# PoE.net
KiCad netlist of a schematic drawn in Altium Designer
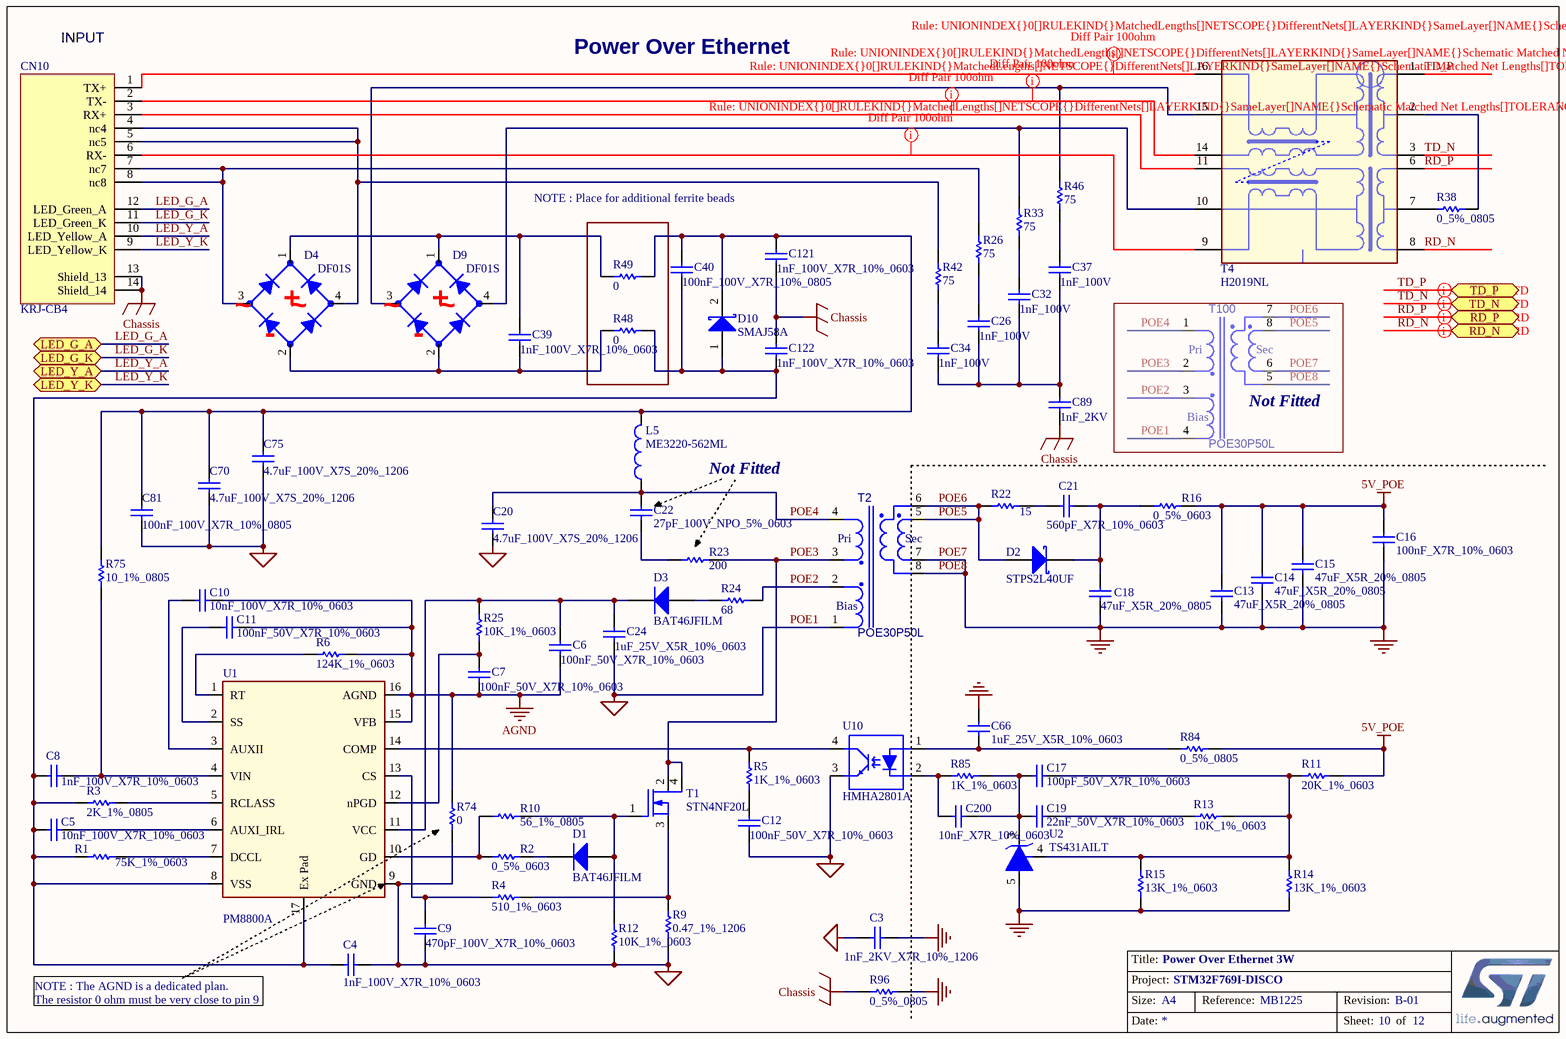
[diagram p0: PoE.SchDoc]

(export (version "E")
  (design (tool "Eeschema 10.0.6"))
  (components
    (comp (ref "C3")
      (value "1nF_2KV_X7R_10%_1206")
      (footprint "1206C")
      (description "Capacitor,1nF,2KV,X7R,10%,1206,YAGEO")
      (libsource (lib "MCD_TOOLS_CAPACITOR") (part "Cap_1nF_2KV_X7R_10%_1206"))
    )
    (comp (ref "C4")
      (value "1nF_100V_X7R_10%_0603")
      (footprint "0603C")
      (description "Capacitor,1nF,100V,X7R,10%,0603,YAGEO")
      (libsource (lib "MCD_TOOLS_CAPACITOR") (part "Cap_1nF_100V_X7R_10%_0603"))
    )
    (comp (ref "C5")
      (value "10nF_100V_X7R_10%_0603")
      (footprint "0603C")
      (description "Capacitor,10nF,100V,X7R,10%,0603,YAGEO")
      (libsource (lib "MCD_TOOLS_CAPACITOR") (part "Cap_10nF_100V_X7R_10%_0603"))
    )
    (comp (ref "C6")
      (value "100nF_50V_X7R_10%_0603")
      (footprint "0603C")
      (description "Capacitor,100nF,50V,X7R,10%,0603,YAGEO")
      (libsource (lib "MCD_TOOLS_CAPACITOR") (part "Cap_100nF_50V_X7R_10%_0603"))
    )
    (comp (ref "C7")
      (value "100nF_50V_X7R_10%_0603")
      (footprint "0603C")
      (description "Capacitor,100nF,50V,X7R,10%,0603,YAGEO")
      (libsource (lib "MCD_TOOLS_CAPACITOR") (part "Cap_100nF_50V_X7R_10%_0603"))
    )
    (comp (ref "C8")
      (value "1nF_100V_X7R_10%_0603")
      (footprint "0603C")
      (description "Capacitor,1nF,100V,X7R,10%,0603,YAGEO")
      (libsource (lib "MCD_TOOLS_CAPACITOR") (part "Cap_1nF_100V_X7R_10%_0603"))
    )
    (comp (ref "C9")
      (value "470pF_100V_X7R_10%_0603")
      (footprint "0603C")
      (description "Capacitor,470pF,100V,X7R,10%,0603,AVX")
      (libsource (lib "MCD_TOOLS_CAPACITOR") (part "Cap_470pF_100V_X7R_10%_0603"))
    )
    (comp (ref "C10")
      (value "10nF_100V_X7R_10%_0603")
      (footprint "0603C")
      (description "Capacitor,10nF,100V,X7R,10%,0603,YAGEO")
      (libsource (lib "MCD_TOOLS_CAPACITOR") (part "Cap_10nF_100V_X7R_10%_0603"))
    )
    (comp (ref "C11")
      (value "100nF_50V_X7R_10%_0603")
      (footprint "0603C")
      (description "Capacitor,100nF,50V,X7R,10%,0603,YAGEO")
      (libsource (lib "MCD_TOOLS_CAPACITOR") (part "Cap_100nF_50V_X7R_10%_0603"))
    )
    (comp (ref "C12")
      (value "100nF_50V_X7R_10%_0603")
      (footprint "0603C")
      (description "Capacitor,100nF,50V,X7R,10%,0603,YAGEO")
      (libsource (lib "MCD_TOOLS_CAPACITOR") (part "Cap_100nF_50V_X7R_10%_0603"))
    )
    (comp (ref "C13")
      (value "47uF_X5R_20%_0805")
      (footprint "0805C")
      (description "Capacitor,47uF,10V,X5R,20%,0805,MURATA")
      (libsource (lib "MCD_TOOLS_CAPACITOR") (part "Cap_47uF_X5R_20%_0805"))
    )
    (comp (ref "C14")
      (value "47uF_X5R_20%_0805")
      (footprint "0805C")
      (description "Capacitor,47uF,10V,X5R,20%,0805,MURATA")
      (libsource (lib "MCD_TOOLS_CAPACITOR") (part "Cap_47uF_X5R_20%_0805"))
    )
    (comp (ref "C15")
      (value "47uF_X5R_20%_0805")
      (footprint "0805C")
      (description "Capacitor,47uF,10V,X5R,20%,0805,MURATA")
      (libsource (lib "MCD_TOOLS_CAPACITOR") (part "Cap_47uF_X5R_20%_0805"))
    )
    (comp (ref "C16")
      (value "100nF_X7R_10%_0603")
      (footprint "0603C")
      (description "Capacitor,100nF,16V,X7R,10%,0603,YAGEO")
      (libsource (lib "MCD_TOOLS_CAPACITOR") (part "Cap_100nF_X7R_10%_0603"))
    )
    (comp (ref "C17")
      (value "100pF_50V_X7R_10%_0603")
      (footprint "0603C")
      (description "Capacitor,100pF,50V,X7R,10%,0603,AVX")
      (libsource (lib "MCD_TOOLS_CAPACITOR") (part "Cap_100pF_50V_X7R_10%_0603"))
    )
    (comp (ref "C18")
      (value "47uF_X5R_20%_0805")
      (footprint "0805C")
      (description "Capacitor,47uF,10V,X5R,20%,0805,MURATA")
      (libsource (lib "MCD_TOOLS_CAPACITOR") (part "Cap_47uF_X5R_20%_0805"))
    )
    (comp (ref "C19")
      (value "22nF_50V_X7R_10%_0603")
      (footprint "0603C")
      (description "Capacitor,22nF,50V,X7R,10%,0603,YAGEO")
      (libsource (lib "MCD_TOOLS_CAPACITOR") (part "Cap_22nF_50V_X7R_10%_0603"))
    )
    (comp (ref "C20")
      (value "4.7uF_100V_X7S_20%_1206")
      (footprint "1206C")
      (description "Capacitor,4.7uF,100V, X7S,20%,1206,AVX")
      (libsource (lib "MCD_TOOLS_CAPACITOR") (part "Cap_4.7uF_100V_X7S_20%_1206"))
    )
    (comp (ref "C21")
      (value "560pF_X7R_10%_0603")
      (footprint "0603C")
      (description "Capacitor,560pF,16V,X7R,10%,0603,AVX")
      (libsource (lib "MCD_TOOLS_CAPACITOR") (part "Cap_560pF_X7R_10%_0603"))
    )
    (comp (ref "C22")
      (value "27pF_100V_NPO_5%_0603")
      (footprint "0603C")
      (description "Capacitor,27pF,100V,NPO,5%,0603,YAGEO")
      (libsource (lib "MCD_TOOLS_CAPACITOR") (part "Cap_27pF_100V_NPO_5%_0603"))
    )
    (comp (ref "C24")
      (value "1uF_25V_X5R_10%_0603")
      (footprint "0603C")
      (description "Capacitor,1uF,25V,X5R,10%,0603,YAGEO")
      (libsource (lib "MCD_TOOLS_CAPACITOR") (part "Cap_1uF_25V_X5R_10%_0603"))
    )
    (comp (ref "C26")
      (value "1nF_100V")
      (footprint "0603C")
      (description "Capacitor,1nF,100V,X7R,10%,0603,YAGEO")
      (libsource (lib "MCD_TOOLS_CAPACITOR") (part "Cap_1nF_100V_X7R_10%_0603"))
    )
    (comp (ref "C32")
      (value "1nF_100V")
      (footprint "0603C")
      (description "Capacitor,1nF,100V,X7R,10%,0603,YAGEO")
      (libsource (lib "MCD_TOOLS_CAPACITOR") (part "Cap_1nF_100V_X7R_10%_0603"))
    )
    (comp (ref "C34")
      (value "1nF_100V")
      (footprint "0603C")
      (description "Capacitor,1nF,100V,X7R,10%,0603,YAGEO")
      (libsource (lib "MCD_TOOLS_CAPACITOR") (part "Cap_1nF_100V_X7R_10%_0603"))
    )
    (comp (ref "C37")
      (value "1nF_100V")
      (footprint "0603C")
      (description "Capacitor,1nF,100V,X7R,10%,0603,YAGEO")
      (libsource (lib "MCD_TOOLS_CAPACITOR") (part "Cap_1nF_100V_X7R_10%_0603"))
    )
    (comp (ref "C39")
      (value "1nF_100V_X7R_10%_0603")
      (footprint "0603C")
      (description "Capacitor,1nF,100V,X7R,10%,0603,YAGEO")
      (libsource (lib "MCD_TOOLS_CAPACITOR") (part "Cap_1nF_100V_X7R_10%_0603"))
    )
    (comp (ref "C40")
      (value "100nF_100V_X7R_10%_0805")
      (footprint "0805C")
      (description "Capacitor,100nF,100V,X7R,10%,0805,TDK")
      (libsource (lib "MCD_TOOLS_CAPACITOR") (part "Cap_100nF_100V_X7R_10%_0805"))
    )
    (comp (ref "C66")
      (value "1uF_25V_X5R_10%_0603")
      (footprint "0603C")
      (description "Capacitor,1uF,25V,X5R,10%,0603,YAGEO")
      (libsource (lib "MCD_TOOLS_CAPACITOR") (part "Cap_1uF_25V_X5R_10%_0603"))
    )
    (comp (ref "C70")
      (value "4.7uF_100V_X7S_20%_1206")
      (footprint "1206C")
      (description "Capacitor,4.7uF,100V, X7S,20%,1206,AVX")
      (libsource (lib "MCD_TOOLS_CAPACITOR") (part "Cap_4.7uF_100V_X7S_20%_1206"))
    )
    (comp (ref "C75")
      (value "4.7uF_100V_X7S_20%_1206")
      (footprint "1206C")
      (description "Capacitor,4.7uF,100V, X7S,20%,1206,AVX")
      (libsource (lib "MCD_TOOLS_CAPACITOR") (part "Cap_4.7uF_100V_X7S_20%_1206"))
    )
    (comp (ref "C81")
      (value "100nF_100V_X7R_10%_0805")
      (footprint "0805C")
      (description "Capacitor,100nF,100V,X7R,10%,0805,TDK")
      (libsource (lib "MCD_TOOLS_CAPACITOR") (part "Cap_100nF_100V_X7R_10%_0805"))
    )
    (comp (ref "C89")
      (value "1nF_2KV")
      (footprint "1206C")
      (description "Capacitor,1nF,2KV,X7R,10%,1206,YAGEO")
      (libsource (lib "MCD_TOOLS_CAPACITOR") (part "Cap_1nF_2KV_X7R_10%_1206"))
    )
    (comp (ref "C121")
      (value "1nF_100V_X7R_10%_0603")
      (footprint "0603C")
      (description "Capacitor,1nF,100V,X7R,10%,0603,YAGEO")
      (libsource (lib "MCD_TOOLS_CAPACITOR") (part "Cap_1nF_100V_X7R_10%_0603"))
    )
    (comp (ref "C122")
      (value "1nF_100V_X7R_10%_0603")
      (footprint "0603C")
      (description "Capacitor,1nF,100V,X7R,10%,0603,YAGEO")
      (libsource (lib "MCD_TOOLS_CAPACITOR") (part "Cap_1nF_100V_X7R_10%_0603"))
    )
    (comp (ref "C200")
      (value "10nF_X7R_10%_0603")
      (footprint "0603C")
      (description "Capacitor,10nF,50V,X7R,10%,0603,YAGEO")
      (libsource (lib "MCD_TOOLS_CAPACITOR") (part "Cap_10nF_X7R_10%_0603"))
    )
    (comp (ref "CN10")
      (value "KRJ-CB4")
      (footprint "RJ45_LED_KRJ-CB4R2GYZNL_EM")
      (description "e-TX (Fast Ethernet)  RJ45 single port (1x1) with LEDS Integrated Connector")
      (libsource (lib "MCD_TOOLS_CONNECTOR") (part "KRJ-CB4"))
    )
    (comp (ref "D1")
      (value "BAT46JFILM")
      (footprint "SOD-323")
      (description "Schottky Single diode(150mA, 100V)")
      (libsource (lib "MCD_TOOLS_MISCELLANEOUS") (part "BAT46JFILM"))
    )
    (comp (ref "D2")
      (value "STPS2L40UF")
      (footprint "SMB")
      (description "Low drop power Schottky rectifier(2A, 40V, 0.34V)")
      (libsource (lib "MCD_TOOLS_MISCELLANEOUS") (part "STPS2L40UF"))
    )
    (comp (ref "D3")
      (value "BAT46JFILM")
      (footprint "SOD-323")
      (description "Schottky Single diode(150mA, 100V)")
      (libsource (lib "MCD_TOOLS_MISCELLANEOUS") (part "BAT46JFILM"))
    )
    (comp (ref "D4")
      (value "DF01S")
      (footprint "DBS101-107G")
      (description "Surface Mount Bridge Rectifiers")
      (libsource (lib "MCD_TOOLS_MISCELLANEOUS") (part "DF01S_SMD"))
    )
    (comp (ref "D9")
      (value "DF01S")
      (footprint "DBS101-107G")
      (description "Surface Mount Bridge Rectifiers")
      (libsource (lib "MCD_TOOLS_MISCELLANEOUS") (part "DF01S_SMD"))
    )
    (comp (ref "D10")
      (value "SMAJ58A")
      (footprint "SMA")
      (description "Transil 400W, VRM=58V")
      (libsource (lib "MCD_TOOLS_MISCELLANEOUS") (part "SMAJ58A"))
    )
    (comp (ref "L5")
      (value "ME3220-562ML")
      (footprint "LSM2_3R2X2R8_H2")
      (description "Power Inductor, 5.6uH, 0.2R, ME3220-562ML, CoilCraft")
      (libsource (lib "MCD_TOOLS_MISCELLANEOUS") (part "ME3220-562ML"))
    )
    (comp (ref "R1")
      (value "75K_1%_0603")
      (footprint "0603R")
      (description "Resistor,75K,0603,1%,YAGEO")
      (libsource (lib "MCD_TOOLS_RESISTOR") (part "Res_75K_1%_0603"))
    )
    (comp (ref "R2")
      (value "0_5%_0603")
      (footprint "0603R-GS")
      (description "Resistor,0,0603,5%,YAGEO")
      (libsource (lib "MCD_TOOLS_RESISTOR") (part "Res_0_5%_0603"))
    )
    (comp (ref "R3")
      (value "2K_1%_0805")
      (footprint "0805R")
      (description "Resistor,2K,0805,1%,YAGEO")
      (libsource (lib "MCD_TOOLS_RESISTOR") (part "Res_2K_1%_0805"))
    )
    (comp (ref "R4")
      (value "510_1%_0603")
      (footprint "0603R")
      (description "Resistor,510,0603,1%,YAGEO")
      (libsource (lib "MCD_TOOLS_RESISTOR") (part "Res_510_1%_0603"))
    )
    (comp (ref "R5")
      (value "1K_1%_0603")
      (footprint "0603R")
      (description "Resistor,1K,0603,1%,YAGEO")
      (libsource (lib "MCD_TOOLS_RESISTOR") (part "Res_1K_1%_0603"))
    )
    (comp (ref "R6")
      (value "124K_1%_0603")
      (footprint "0603R")
      (description "Resistor,124K,0603,1%,YAGEO")
      (libsource (lib "MCD_TOOLS_RESISTOR") (part "Res_124K_1%_0603"))
    )
    (comp (ref "R9")
      (value "0.47_1%_1206")
      (footprint "1206R")
      (description "Resistor,0.47,1206,1%,YAGEO")
      (libsource (lib "MCD_TOOLS_RESISTOR") (part "Res_0.47_1%_1206"))
    )
    (comp (ref "R10")
      (value "56_1%_0805")
      (footprint "0805R")
      (description "Resistor,56,0805,1%,YAGEO")
      (libsource (lib "MCD_TOOLS_RESISTOR") (part "Res_56_1%_0805"))
    )
    (comp (ref "R11")
      (value "20K_1%_0603")
      (footprint "0603R")
      (description "Resistor,20K,0603,1%,YAGEO")
      (libsource (lib "MCD_TOOLS_RESISTOR") (part "Res_20K_1%_0603"))
    )
    (comp (ref "R12")
      (value "10K_1%_0603")
      (footprint "0603R")
      (description "Resistor,10K,0603,1%,YAGEO")
      (libsource (lib "MCD_TOOLS_RESISTOR") (part "Res_10K_1%_0603"))
    )
    (comp (ref "R13")
      (value "10K_1%_0603")
      (footprint "0603R")
      (description "Resistor,10K,0603,1%,YAGEO")
      (libsource (lib "MCD_TOOLS_RESISTOR") (part "Res_10K_1%_0603"))
    )
    (comp (ref "R14")
      (value "13K_1%_0603")
      (footprint "0603R")
      (description "Resistor,13K,0603,1%,YAGEO")
      (libsource (lib "MCD_TOOLS_RESISTOR") (part "Res_13K_1%_0603"))
    )
    (comp (ref "R15")
      (value "13K_1%_0603")
      (footprint "0603R")
      (description "Resistor,13K,0603,1%,YAGEO")
      (libsource (lib "MCD_TOOLS_RESISTOR") (part "Res_13K_1%_0603"))
    )
    (comp (ref "R16")
      (value "0_5%_0603")
      (footprint "0603R-GS")
      (description "Resistor,0,0603,5%,YAGEO")
      (libsource (lib "MCD_TOOLS_RESISTOR") (part "Res_0_5%_0603"))
    )
    (comp (ref "R22")
      (value "15")
      (footprint "0805R")
      (description "Resistor,15,0805,1%,YAGEO")
      (libsource (lib "MCD_TOOLS_RESISTOR") (part "Res_15_1%_0805"))
    )
    (comp (ref "R23")
      (value "200")
      (footprint "1206R")
      (description "Resistor,200,1206,1%,Rohm")
      (libsource (lib "MCD_TOOLS_RESISTOR") (part "Res_200_1%_1206"))
    )
    (comp (ref "R24")
      (value "68")
      (footprint "0805R")
      (description "Resistor,68,0805,1%,YAGEO")
      (libsource (lib "MCD_TOOLS_RESISTOR") (part "Res_68_1%_0805"))
    )
    (comp (ref "R25")
      (value "10K_1%_0603")
      (footprint "0603R")
      (description "Resistor,10K,0603,1%,YAGEO")
      (libsource (lib "MCD_TOOLS_RESISTOR") (part "Res_10K_1%_0603"))
    )
    (comp (ref "R26")
      (value "75")
      (footprint "0805R")
      (description "Resistor,75,0805,1%,YAGEO")
      (libsource (lib "MCD_TOOLS_RESISTOR") (part "Res_75_1%_0805"))
    )
    (comp (ref "R33")
      (value "75")
      (footprint "0805R")
      (description "Resistor,75,0805,1%,YAGEO")
      (libsource (lib "MCD_TOOLS_RESISTOR") (part "Res_75_1%_0805"))
    )
    (comp (ref "R38")
      (value "0_5%_0805")
      (footprint "0805R")
      (description "Resistor,0,0805,5%,YAGEO")
      (libsource (lib "MCD_TOOLS_RESISTOR") (part "Res_0_5%_0805"))
    )
    (comp (ref "R42")
      (value "75")
      (footprint "0805R")
      (description "Resistor,75,0805,1%,YAGEO")
      (libsource (lib "MCD_TOOLS_RESISTOR") (part "Res_75_1%_0805"))
    )
    (comp (ref "R46")
      (value "75")
      (footprint "0805R")
      (description "Resistor,75,0805,1%,YAGEO")
      (libsource (lib "MCD_TOOLS_RESISTOR") (part "Res_75_1%_0805"))
    )
    (comp (ref "R48")
      (value "0")
      (footprint "0805R")
      (description "Resistor,0,0805,5%,YAGEO")
      (libsource (lib "MCD_TOOLS_RESISTOR") (part "Res_0_5%_0805"))
    )
    (comp (ref "R49")
      (value "0")
      (footprint "0805R")
      (description "Resistor,0,0805,5%,YAGEO")
      (libsource (lib "MCD_TOOLS_RESISTOR") (part "Res_0_5%_0805"))
    )
    (comp (ref "R74")
      (value "0")
      (footprint "0603R-GS")
      (description "Resistor,0,0603,5%,YAGEO")
      (libsource (lib "MCD_TOOLS_RESISTOR") (part "Res_0_5%_0603"))
    )
    (comp (ref "R75")
      (value "10_1%_0805")
      (footprint "0805R")
      (description "Resistor,10,0805,1%,Stackpole,1/4W")
      (libsource (lib "MCD_TOOLS_RESISTOR") (part "Res_10_1%_0805"))
    )
    (comp (ref "R84")
      (value "0_5%_0805")
      (footprint "0805R")
      (description "Resistor,0,0805,5%,YAGEO")
      (libsource (lib "MCD_TOOLS_RESISTOR") (part "Res_0_5%_0805"))
    )
    (comp (ref "R85")
      (value "1K_1%_0603")
      (footprint "0603R")
      (description "Resistor,1K,0603,1%,YAGEO")
      (libsource (lib "MCD_TOOLS_RESISTOR") (part "Res_1K_1%_0603"))
    )
    (comp (ref "R96")
      (value "0_5%_0805")
      (footprint "0805R")
      (description "Resistor,0,0805,5%,YAGEO")
      (libsource (lib "MCD_TOOLS_RESISTOR") (part "Res_0_5%_0805"))
    )
    (comp (ref "T1")
      (value "STN4NF20L")
      (footprint "SOT-223")
      (description "N-channel 200 V, 1.1ohm, 1 A, low gate charge STripFET II, Power MOSFET")
      (libsource (lib "MCD_TOOLS_MISCELLANEOUS") (part "STN4NF20L"))
    )
    (comp (ref "T2")
      (value "POE30P50L")
      (footprint "TF_10R9X13R2-12R2X14R4_CPT")
      (description "Flyback Transformers for 3 Watt, PoE applications, CoilCraft Cyntec")
      (fields (field (name "PROVIDED") "Sub Co"))
      (libsource (lib "MCD_TOOLS_MISCELLANEOUS") (part "POE30P_C"))
    )
    (comp (ref "T4")
      (value "H2019NL")
      (footprint "TF_16SM_12R7X9R65")
      (description "10/100BASE-TX VoIP Magnetics Modules, Data Transformer")
      (libsource (lib "MCD_TOOLS_MISCELLANEOUS") (part "H2019"))
    )
    (comp (ref "T100")
      (value "POE30P50L")
      (footprint "TF_8SM_12R04X12R85")
      (description "Flyback Transformers for 3 Watt, PoE applications, Wurth")
      (fields (field (name "PROVIDED") "Sub Co"))
      (libsource (lib "MCD_TOOLS_MISCELLANEOUS") (part "POE30P_W"))
    )
    (comp (ref "U1")
      (value "PM8800A")
      (footprint "TSSOP16_0R65_5x6R4_TP")
      (fields (field (name "PROVIDED") "STM"))
      (libsource (lib "MCD_TOOLS_MISCELLANEOUS") (part "PM8800A"))
    )
    (comp (ref "U2")
      (value "TS431AILT")
      (footprint "SOT23-5")
      (description "Low voltage adjustable shunt reference")
      (libsource (lib "MCD_TOOLS_MISCELLANEOUS") (part "TS431AILT"))
    )
    (comp (ref "U10")
      (value "HMHA2801A")
      (footprint "PC_4SM_1R27_2R5X6R8")
      (description "OPTOISOLATOR 3.7KV TRANSISTOR 4SMD")
      (libsource (lib "MCD_TOOLS_MISCELLANEOUS") (part "HMHA2801A"))
    )
  )
  (nets
    (net (code "1") (name "/LED_G_A") (class "Default")
      (node (ref "CN10") (pin "12") (pinfunction "LED_Green_A_12") (pintype "passive"))
    )
    (net (code "2") (name "/LED_G_K") (class "Default")
      (node (ref "CN10") (pin "11") (pinfunction "LED_Green_K_11") (pintype "passive"))
    )
    (net (code "3") (name "/LED_Y_A") (class "Default")
      (node (ref "CN10") (pin "10") (pinfunction "LED_Yellow_A_10") (pintype "passive"))
    )
    (net (code "4") (name "/LED_Y_K") (class "Default")
      (node (ref "CN10") (pin "9") (pinfunction "LED_Yellow_K_9") (pintype "passive"))
    )
    (net (code "5") (name "/POE2") (class "Default")
      (node (ref "R24") (pin "2") (pinfunction "2_2") (pintype "passive"))
      (node (ref "T100") (pin "3") (pinfunction "3_3") (pintype "passive"))
      (node (ref "T2") (pin "2") (pinfunction "2_2") (pintype "passive"))
    )
    (net (code "6") (name "/POE3") (class "Default")
      (node (ref "R23") (pin "2") (pinfunction "2_2") (pintype "passive"))
      (node (ref "T1") (pin "2") (pinfunction "D_2") (pintype "passive"))
      (node (ref "T1") (pin "4") (pinfunction "D_4") (pintype "passive"))
      (node (ref "T100") (pin "2") (pinfunction "2_2") (pintype "passive"))
      (node (ref "T2") (pin "3") (pinfunction "3_3") (pintype "passive"))
    )
    (net (code "7") (name "/POE4") (class "Default")
      (node (ref "C20") (pin "2") (pinfunction "2_2") (pintype "passive"))
      (node (ref "C22") (pin "2") (pinfunction "2_2") (pintype "passive"))
      (node (ref "L5") (pin "1") (pinfunction "1_1") (pintype "passive"))
      (node (ref "T100") (pin "1") (pinfunction "1_1") (pintype "passive"))
      (node (ref "T2") (pin "4") (pinfunction "4_4") (pintype "passive"))
    )
    (net (code "8") (name "/POE5") (class "Default")
      (node (ref "D2") (pin "1") (pinfunction "A_1") (pintype "passive"))
      (node (ref "R22") (pin "1") (pinfunction "1_1") (pintype "passive"))
      (node (ref "T100") (pin "7") (pinfunction "7_7") (pintype "passive"))
      (node (ref "T100") (pin "8") (pinfunction "8_8") (pintype "passive"))
      (node (ref "T2") (pin "5") (pinfunction "5_5") (pintype "passive"))
      (node (ref "T2") (pin "6") (pinfunction "6_6") (pintype "passive"))
    )
    (net (code "9") (name "/RD_N") (class "Default")
      (node (ref "T4") (pin "8") (pinfunction "rd-_8") (pintype "passive"))
    )
    (net (code "10") (name "/RD_P") (class "Default")
      (node (ref "T4") (pin "6") (pinfunction "rd+_6") (pintype "passive"))
    )
    (net (code "11") (name "/TD_N") (class "Default")
      (node (ref "T4") (pin "3") (pinfunction "td-_3") (pintype "passive"))
    )
    (net (code "12") (name "/TD_P") (class "Default")
      (node (ref "T4") (pin "1") (pinfunction "td+_1") (pintype "passive"))
    )
    (net (code "13") (name "5V_POE") (class "Default")
      (node (ref "C13") (pin "2") (pinfunction "2_2") (pintype "passive"))
      (node (ref "C14") (pin "2") (pinfunction "2_2") (pintype "passive"))
      (node (ref "C15") (pin "2") (pinfunction "2_2") (pintype "passive"))
      (node (ref "C16") (pin "2") (pinfunction "2_2") (pintype "passive"))
      (node (ref "R11") (pin "2") (pinfunction "2_2") (pintype "passive"))
      (node (ref "R16") (pin "2") (pinfunction "2_2") (pintype "passive"))
      (node (ref "R84") (pin "2") (pinfunction "2_2") (pintype "passive"))
    )
    (net (code "14") (name "AGND") (class "Default")
      (node (ref "C10") (pin "2") (pinfunction "2_2") (pintype "passive"))
      (node (ref "C11") (pin "2") (pinfunction "2_2") (pintype "passive"))
      (node (ref "C6") (pin "1") (pinfunction "1_1") (pintype "passive"))
      (node (ref "C7") (pin "1") (pinfunction "1_1") (pintype "passive"))
      (node (ref "R6") (pin "2") (pinfunction "2_2") (pintype "passive"))
      (node (ref "R74") (pin "2") (pinfunction "2_2") (pintype "passive"))
      (node (ref "U1") (pin "15") (pinfunction "VFB_15") (pintype "passive"))
      (node (ref "U1") (pin "16") (pinfunction "AGND_16") (pintype "passive"))
    )
    (net (code "15") (name "Chassis") (class "Default")
      (node (ref "C121") (pin "1") (pinfunction "1_1") (pintype "passive"))
      (node (ref "C122") (pin "2") (pinfunction "2_2") (pintype "passive"))
      (node (ref "C89") (pin "1") (pinfunction "1_1") (pintype "passive"))
      (node (ref "CN10") (pin "13") (pinfunction "Shield_13_13") (pintype "passive"))
      (node (ref "CN10") (pin "14") (pinfunction "Shield_14_14") (pintype "passive"))
      (node (ref "R96") (pin "1") (pinfunction "1_1") (pintype "passive"))
    )
    (net (code "16") (name "GND") (class "Default")
      (node (ref "C13") (pin "1") (pinfunction "1_1") (pintype "passive"))
      (node (ref "C14") (pin "1") (pinfunction "1_1") (pintype "passive"))
      (node (ref "C15") (pin "1") (pinfunction "1_1") (pintype "passive"))
      (node (ref "C16") (pin "1") (pinfunction "1_1") (pintype "passive"))
      (node (ref "C18") (pin "1") (pinfunction "1_1") (pintype "passive"))
      (node (ref "C3") (pin "2") (pinfunction "2_2") (pintype "passive"))
      (node (ref "C66") (pin "2") (pinfunction "2_2") (pintype "passive"))
      (node (ref "R14") (pin "1") (pinfunction "1_1") (pintype "passive"))
      (node (ref "R15") (pin "1") (pinfunction "1_1") (pintype "passive"))
      (node (ref "R96") (pin "2") (pinfunction "2_2") (pintype "passive"))
      (node (ref "T100") (pin "5") (pinfunction "5_5") (pintype "passive"))
      (node (ref "T100") (pin "6") (pinfunction "6_6") (pintype "passive"))
      (node (ref "T2") (pin "7") (pinfunction "7_7") (pintype "passive"))
      (node (ref "T2") (pin "8") (pinfunction "8_8") (pintype "passive"))
      (node (ref "U2") (pin "5") (pinfunction "A_5") (pintype "passive"))
    )
    (net (code "17") (name "GND_POWER_IN") (class "Default")
      (node (ref "C12") (pin "1") (pinfunction "1_1") (pintype "passive"))
      (node (ref "C20") (pin "1") (pinfunction "1_1") (pintype "passive"))
      (node (ref "C24") (pin "1") (pinfunction "1_1") (pintype "passive"))
      (node (ref "C3") (pin "1") (pinfunction "1_1") (pintype "passive"))
      (node (ref "C4") (pin "2") (pinfunction "2_2") (pintype "passive"))
      (node (ref "C70") (pin "1") (pinfunction "1_1") (pintype "passive"))
      (node (ref "C75") (pin "1") (pinfunction "1_1") (pintype "passive"))
      (node (ref "C81") (pin "1") (pinfunction "1_1") (pintype "passive"))
      (node (ref "C9") (pin "1") (pinfunction "1_1") (pintype "passive"))
      (node (ref "R12") (pin "1") (pinfunction "1_1") (pintype "passive"))
      (node (ref "R74") (pin "1") (pinfunction "1_1") (pintype "passive"))
      (node (ref "R9") (pin "1") (pinfunction "1_1") (pintype "passive"))
      (node (ref "T100") (pin "4") (pinfunction "4_4") (pintype "passive"))
      (node (ref "T2") (pin "1") (pinfunction "1_1") (pintype "passive"))
      (node (ref "U1") (pin "9") (pinfunction "GND_9") (pintype "passive"))
      (node (ref "U10") (pin "3") (pinfunction "Emitter_3") (pintype "passive"))
    )
    (net (code "18") (name "Net-(C12-Pad2)") (class "Default")
      (node (ref "C12") (pin "2") (pinfunction "2_2") (pintype "passive"))
      (node (ref "R5") (pin "1") (pinfunction "1_1") (pintype "passive"))
    )
    (net (code "19") (name "Net-(C19-Pad2)") (class "Default")
      (node (ref "C19") (pin "2") (pinfunction "2_2") (pintype "passive"))
      (node (ref "R13") (pin "1") (pinfunction "1_1") (pintype "passive"))
    )
    (net (code "20") (name "Net-(C21-Pad1)") (class "Default")
      (node (ref "C21") (pin "1") (pinfunction "1_1") (pintype "passive"))
      (node (ref "R22") (pin "2") (pinfunction "2_2") (pintype "passive"))
    )
    (net (code "21") (name "Net-(C22-Pad1)") (class "Default")
      (node (ref "C22") (pin "1") (pinfunction "1_1") (pintype "passive"))
      (node (ref "R23") (pin "1") (pinfunction "1_1") (pintype "passive"))
    )
    (net (code "22") (name "Net-(C26-Pad1)") (class "Default")
      (node (ref "C26") (pin "1") (pinfunction "1_1") (pintype "passive"))
      (node (ref "C32") (pin "1") (pinfunction "1_1") (pintype "passive"))
      (node (ref "C34") (pin "1") (pinfunction "1_1") (pintype "passive"))
      (node (ref "C37") (pin "1") (pinfunction "1_1") (pintype "passive"))
      (node (ref "C89") (pin "2") (pinfunction "2_2") (pintype "passive"))
    )
    (net (code "23") (name "Net-(C26-Pad2)") (class "Default")
      (node (ref "C26") (pin "2") (pinfunction "2_2") (pintype "passive"))
      (node (ref "R26") (pin "1") (pinfunction "1_1") (pintype "passive"))
    )
    (net (code "24") (name "Net-(C32-Pad2)") (class "Default")
      (node (ref "C32") (pin "2") (pinfunction "2_2") (pintype "passive"))
      (node (ref "R33") (pin "1") (pinfunction "1_1") (pintype "passive"))
    )
    (net (code "25") (name "Net-(C34-Pad2)") (class "Default")
      (node (ref "C34") (pin "2") (pinfunction "2_2") (pintype "passive"))
      (node (ref "R42") (pin "1") (pinfunction "1_1") (pintype "passive"))
    )
    (net (code "26") (name "Net-(C37-Pad2)") (class "Default")
      (node (ref "C37") (pin "2") (pinfunction "2_2") (pintype "passive"))
      (node (ref "R46") (pin "1") (pinfunction "1_1") (pintype "passive"))
    )
    (net (code "27") (name "Net-(CN10-RX+)") (class "Default")
      (node (ref "CN10") (pin "3") (pinfunction "RX+_3") (pintype "passive"))
      (node (ref "T4") (pin "11") (pinfunction "rx1+_11") (pintype "passive"))
    )
    (net (code "28") (name "Net-(CN10-RX-)") (class "Default")
      (node (ref "CN10") (pin "6") (pinfunction "RX-_6") (pintype "passive"))
      (node (ref "T4") (pin "9") (pinfunction "rx-_9") (pintype "passive"))
    )
    (net (code "29") (name "Net-(CN10-TX+)") (class "Default")
      (node (ref "CN10") (pin "1") (pinfunction "TX+_1") (pintype "passive"))
      (node (ref "T4") (pin "16") (pinfunction "tx1+_16") (pintype "passive"))
    )
    (net (code "30") (name "Net-(CN10-TX-)") (class "Default")
      (node (ref "CN10") (pin "2") (pinfunction "TX-_2") (pintype "passive"))
      (node (ref "T4") (pin "14") (pinfunction "tx1-_14") (pintype "passive"))
    )
    (net (code "31") (name "Net-(CN10-nc4)") (class "Default")
      (node (ref "CN10") (pin "4") (pinfunction "nc4_4") (pintype "passive"))
      (node (ref "CN10") (pin "5") (pinfunction "nc5_5") (pintype "passive"))
      (node (ref "D4") (pin "4") (pinfunction "AC_IN_1_4") (pintype "passive"))
      (node (ref "R42") (pin "2") (pinfunction "2_2") (pintype "passive"))
    )
    (net (code "32") (name "Net-(CN10-nc7)") (class "Default")
      (node (ref "CN10") (pin "7") (pinfunction "nc7_7") (pintype "passive"))
      (node (ref "CN10") (pin "8") (pinfunction "nc8_8") (pintype "passive"))
      (node (ref "D4") (pin "3") (pinfunction "AC_IN_2_3") (pintype "passive"))
      (node (ref "R26") (pin "2") (pinfunction "2_2") (pintype "passive"))
    )
    (net (code "33") (name "Net-(D1-A)") (class "Default")
      (node (ref "D1") (pin "1") (pinfunction "A_1") (pintype "passive"))
      (node (ref "R10") (pin "2") (pinfunction "2_2") (pintype "passive"))
      (node (ref "R12") (pin "2") (pinfunction "2_2") (pintype "passive"))
      (node (ref "T1") (pin "1") (pinfunction "G_1") (pintype "passive"))
    )
    (net (code "34") (name "Net-(D1-K)") (class "Default")
      (node (ref "D1") (pin "2") (pinfunction "K_2") (pintype "passive"))
      (node (ref "R2") (pin "2") (pinfunction "2_2") (pintype "passive"))
    )
    (net (code "35") (name "Net-(D2-K)") (class "Default")
      (node (ref "C18") (pin "2") (pinfunction "2_2") (pintype "passive"))
      (node (ref "C21") (pin "2") (pinfunction "2_2") (pintype "passive"))
      (node (ref "D2") (pin "2") (pinfunction "K_2") (pintype "passive"))
      (node (ref "R16") (pin "1") (pinfunction "1_1") (pintype "passive"))
    )
    (net (code "36") (name "Net-(D3-A)") (class "Default")
      (node (ref "D3") (pin "1") (pinfunction "A_1") (pintype "passive"))
      (node (ref "R24") (pin "1") (pinfunction "1_1") (pintype "passive"))
    )
    (net (code "37") (name "Net-(D3-K)") (class "Default")
      (node (ref "C24") (pin "2") (pinfunction "2_2") (pintype "passive"))
      (node (ref "C6") (pin "2") (pinfunction "2_2") (pintype "passive"))
      (node (ref "D3") (pin "2") (pinfunction "K_2") (pintype "passive"))
      (node (ref "R25") (pin "2") (pinfunction "2_2") (pintype "passive"))
      (node (ref "U1") (pin "11") (pinfunction "VCC_11") (pintype "passive"))
    )
    (net (code "38") (name "Net-(D4-DC_OUT_MINUS)") (class "Default")
      (node (ref "C39") (pin "1") (pinfunction "1_1") (pintype "passive"))
      (node (ref "D4") (pin "2") (pinfunction "DC_OUT_MINUS_2") (pintype "passive"))
      (node (ref "D9") (pin "2") (pinfunction "DC_OUT_MINUS_2") (pintype "passive"))
      (node (ref "R48") (pin "1") (pinfunction "1_1") (pintype "passive"))
    )
    (net (code "39") (name "Net-(D4-DC_OUT_PLUS)") (class "Default")
      (node (ref "C39") (pin "2") (pinfunction "2_2") (pintype "passive"))
      (node (ref "D4") (pin "1") (pinfunction "DC_OUT_PLUS_1") (pintype "passive"))
      (node (ref "D9") (pin "1") (pinfunction "DC_OUT_PLUS_1") (pintype "passive"))
      (node (ref "R49") (pin "1") (pinfunction "1_1") (pintype "passive"))
    )
    (net (code "40") (name "Net-(D9-AC_IN_1)") (class "Default")
      (node (ref "D9") (pin "4") (pinfunction "AC_IN_1_4") (pintype "passive"))
      (node (ref "R33") (pin "2") (pinfunction "2_2") (pintype "passive"))
      (node (ref "T4") (pin "10") (pinfunction "rxct_10") (pintype "passive"))
    )
    (net (code "41") (name "Net-(D9-AC_IN_2)") (class "Default")
      (node (ref "D9") (pin "3") (pinfunction "AC_IN_2_3") (pintype "passive"))
      (node (ref "R46") (pin "2") (pinfunction "2_2") (pintype "passive"))
      (node (ref "T4") (pin "15") (pinfunction "txct_15") (pintype "passive"))
    )
    (net (code "42") (name "Net-(D10-A)") (class "Default")
      (node (ref "C122") (pin "1") (pinfunction "1_1") (pintype "passive"))
      (node (ref "C4") (pin "1") (pinfunction "1_1") (pintype "passive"))
      (node (ref "C40") (pin "1") (pinfunction "1_1") (pintype "passive"))
      (node (ref "C5") (pin "1") (pinfunction "1_1") (pintype "passive"))
      (node (ref "C8") (pin "1") (pinfunction "1_1") (pintype "passive"))
      (node (ref "D10") (pin "1") (pinfunction "A_1") (pintype "passive"))
      (node (ref "R1") (pin "1") (pinfunction "1_1") (pintype "passive"))
      (node (ref "R3") (pin "1") (pinfunction "1_1") (pintype "passive"))
      (node (ref "R48") (pin "2") (pinfunction "2_2") (pintype "passive"))
      (node (ref "U1") (pin "17") (pinfunction "Ex_Pad_17") (pintype "passive"))
      (node (ref "U1") (pin "8") (pinfunction "VSS_8") (pintype "passive"))
    )
    (net (code "43") (name "Net-(D10-K)") (class "Default")
      (node (ref "C121") (pin "2") (pinfunction "2_2") (pintype "passive"))
      (node (ref "C40") (pin "2") (pinfunction "2_2") (pintype "passive"))
      (node (ref "C70") (pin "2") (pinfunction "2_2") (pintype "passive"))
      (node (ref "C75") (pin "2") (pinfunction "2_2") (pintype "passive"))
      (node (ref "C81") (pin "2") (pinfunction "2_2") (pintype "passive"))
      (node (ref "D10") (pin "2") (pinfunction "K_2") (pintype "passive"))
      (node (ref "L5") (pin "2") (pinfunction "2_2") (pintype "passive"))
      (node (ref "R49") (pin "2") (pinfunction "2_2") (pintype "passive"))
      (node (ref "R75") (pin "2") (pinfunction "2_2") (pintype "passive"))
    )
    (net (code "44") (name "Net-(T1-S)") (class "Default")
      (node (ref "R4") (pin "2") (pinfunction "2_2") (pintype "passive"))
      (node (ref "R9") (pin "2") (pinfunction "2_2") (pintype "passive"))
      (node (ref "T1") (pin "3") (pinfunction "S_3") (pintype "passive"))
    )
    (net (code "45") (name "Net-(T4-rct)") (class "Default")
      (node (ref "R38") (pin "1") (pinfunction "1_1") (pintype "passive"))
      (node (ref "T4") (pin "7") (pinfunction "rct_7") (pintype "passive"))
    )
    (net (code "46") (name "Net-(T4-tct)") (class "Default")
      (node (ref "R38") (pin "2") (pinfunction "2_2") (pintype "passive"))
      (node (ref "T4") (pin "2") (pinfunction "tct_2") (pintype "passive"))
    )
    (net (code "47") (name "Net-(U1-AUXII)") (class "Default")
      (node (ref "C10") (pin "1") (pinfunction "1_1") (pintype "passive"))
      (node (ref "U1") (pin "3") (pinfunction "AUXII_3") (pintype "passive"))
    )
    (net (code "48") (name "Net-(U1-AUXI_IRL)") (class "Default")
      (node (ref "C5") (pin "2") (pinfunction "2_2") (pintype "passive"))
      (node (ref "U1") (pin "6") (pinfunction "AUXI_IRL_6") (pintype "passive"))
    )
    (net (code "49") (name "Net-(U1-COMP)") (class "Default")
      (node (ref "R5") (pin "2") (pinfunction "2_2") (pintype "passive"))
      (node (ref "U1") (pin "14") (pinfunction "COMP_14") (pintype "passive"))
      (node (ref "U10") (pin "4") (pinfunction "Collector_4") (pintype "passive"))
    )
    (net (code "50") (name "Net-(U1-CS)") (class "Default")
      (node (ref "C9") (pin "2") (pinfunction "2_2") (pintype "passive"))
      (node (ref "R4") (pin "1") (pinfunction "1_1") (pintype "passive"))
      (node (ref "U1") (pin "13") (pinfunction "CS_13") (pintype "passive"))
    )
    (net (code "51") (name "Net-(U1-DCCL)") (class "Default")
      (node (ref "R1") (pin "2") (pinfunction "2_2") (pintype "passive"))
      (node (ref "U1") (pin "7") (pinfunction "DCCL_7") (pintype "passive"))
    )
    (net (code "52") (name "Net-(U1-GD)") (class "Default")
      (node (ref "R10") (pin "1") (pinfunction "1_1") (pintype "passive"))
      (node (ref "R2") (pin "1") (pinfunction "1_1") (pintype "passive"))
      (node (ref "U1") (pin "10") (pinfunction "GD_10") (pintype "passive"))
    )
    (net (code "53") (name "Net-(U1-RCLASS)") (class "Default")
      (node (ref "R3") (pin "2") (pinfunction "2_2") (pintype "passive"))
      (node (ref "U1") (pin "5") (pinfunction "RCLASS_5") (pintype "passive"))
    )
    (net (code "54") (name "Net-(U1-RT)") (class "Default")
      (node (ref "R6") (pin "1") (pinfunction "1_1") (pintype "passive"))
      (node (ref "U1") (pin "1") (pinfunction "RT_1") (pintype "passive"))
    )
    (net (code "55") (name "Net-(U1-SS)") (class "Default")
      (node (ref "C11") (pin "1") (pinfunction "1_1") (pintype "passive"))
      (node (ref "U1") (pin "2") (pinfunction "SS_2") (pintype "passive"))
    )
    (net (code "56") (name "Net-(U1-VIN)") (class "Default")
      (node (ref "C8") (pin "2") (pinfunction "2_2") (pintype "passive"))
      (node (ref "R75") (pin "1") (pinfunction "1_1") (pintype "passive"))
      (node (ref "U1") (pin "4") (pinfunction "VIN_4") (pintype "passive"))
    )
    (net (code "57") (name "Net-(U1-nPGD)") (class "Default")
      (node (ref "C7") (pin "2") (pinfunction "2_2") (pintype "passive"))
      (node (ref "R25") (pin "1") (pinfunction "1_1") (pintype "passive"))
      (node (ref "U1") (pin "12") (pinfunction "nPGD_12") (pintype "passive"))
    )
    (net (code "58") (name "Net-(U2-K)") (class "Default")
      (node (ref "C17") (pin "1") (pinfunction "1_1") (pintype "passive"))
      (node (ref "C19") (pin "1") (pinfunction "1_1") (pintype "passive"))
      (node (ref "C200") (pin "2") (pinfunction "2_2") (pintype "passive"))
      (node (ref "R85") (pin "2") (pinfunction "2_2") (pintype "passive"))
      (node (ref "U2") (pin "3") (pinfunction "K_3") (pintype "passive"))
    )
    (net (code "59") (name "Net-(U2-REF)") (class "Default")
      (node (ref "C17") (pin "2") (pinfunction "2_2") (pintype "passive"))
      (node (ref "R11") (pin "1") (pinfunction "1_1") (pintype "passive"))
      (node (ref "R13") (pin "2") (pinfunction "2_2") (pintype "passive"))
      (node (ref "R14") (pin "2") (pinfunction "2_2") (pintype "passive"))
      (node (ref "R15") (pin "2") (pinfunction "2_2") (pintype "passive"))
      (node (ref "U2") (pin "4") (pinfunction "REF_4") (pintype "passive"))
    )
    (net (code "60") (name "Net-(U10-Anode)") (class "Default")
      (node (ref "C66") (pin "1") (pinfunction "1_1") (pintype "passive"))
      (node (ref "R84") (pin "1") (pinfunction "1_1") (pintype "passive"))
      (node (ref "U10") (pin "1") (pinfunction "Anode_1") (pintype "passive"))
    )
    (net (code "61") (name "Net-(U10-B)") (class "Default")
      (node (ref "C200") (pin "1") (pinfunction "1_1") (pintype "passive"))
      (node (ref "R85") (pin "1") (pinfunction "1_1") (pintype "passive"))
      (node (ref "U10") (pin "2") (pinfunction "B_2") (pintype "passive"))
    )
    (net (code "62") (name "unconnected-(T4-nc_4-Pad4)") (class "Default")
      (node (ref "T4") (pin "4") (pinfunction "nc_4_4") (pintype "passive"))
    )
    (net (code "63") (name "unconnected-(T4-nc_5-Pad5)") (class "Default")
      (node (ref "T4") (pin "5") (pinfunction "nc_5_5") (pintype "passive"))
    )
    (net (code "64") (name "unconnected-(T4-nc_12-Pad12)") (class "Default")
      (node (ref "T4") (pin "12") (pinfunction "nc_12_12") (pintype "passive"))
    )
    (net (code "65") (name "unconnected-(T4-nc_13-Pad13)") (class "Default")
      (node (ref "T4") (pin "13") (pinfunction "nc_13_13") (pintype "passive"))
    )
    (net (code "66") (name "unconnected-(U2-nc_1-Pad1)") (class "Default")
      (node (ref "U2") (pin "1") (pinfunction "nc_1_1") (pintype "passive"))
    )
    (net (code "67") (name "unconnected-(U2-nc_2-Pad2)") (class "Default")
      (node (ref "U2") (pin "2") (pinfunction "nc_2_2") (pintype "passive"))
    )
  )
)
